# LUMINA_BOARD.net
KiCad netlist of a schematic drawn in EAGLE
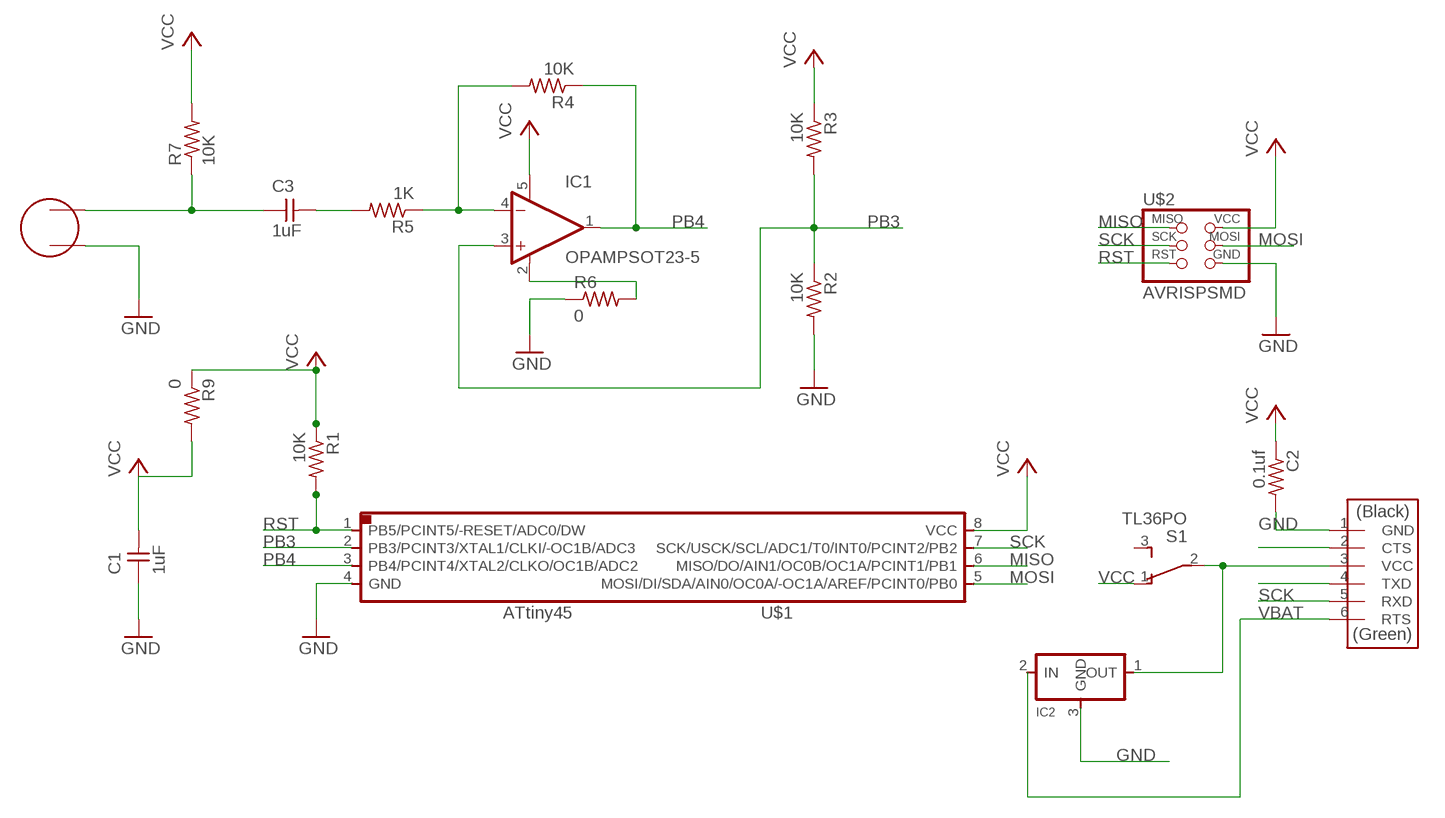
[diagram p0: schematic, sheet 1]

(export (version "E")
  (design (tool "Eeschema 10.0.6"))
  (components
    (comp (ref "C1")
      (value "1uF")
      (footprint "eagle-import:1206")
      (libsource (lib "eagle-import") (part "UNPOLARIZED_CAPACITOR1206"))
    )
    (comp (ref "C2")
      (value "0.1uf")
      (footprint "eagle-import:1206")
      (libsource (lib "eagle-import") (part "RESISTOR1206"))
    )
    (comp (ref "C3")
      (value "1uF")
      (footprint "eagle-import:1206")
      (libsource (lib "eagle-import") (part "UNPOLARIZED_CAPACITOR1206"))
    )
    (comp (ref "IC1")
      (value "OPAMPSOT23-5")
      (footprint "eagle-import:SOT23-5")
      (libsource (lib "eagle-import") (part "OPAMPSOT23-5"))
    )
    (comp (ref "IC2")
      (value "REGULATORSOT23")
      (footprint "eagle-import:SOT23")
      (libsource (lib "eagle-import") (part "REGULATORSOT23"))
    )
    (comp (ref "R1")
      (value "10K")
      (footprint "eagle-import:1206")
      (libsource (lib "eagle-import") (part "RESISTOR1206"))
    )
    (comp (ref "R2")
      (value "10K")
      (footprint "eagle-import:1206")
      (libsource (lib "eagle-import") (part "RESISTOR1206"))
    )
    (comp (ref "R3")
      (value "10K")
      (footprint "eagle-import:1206")
      (libsource (lib "eagle-import") (part "RESISTOR1206"))
    )
    (comp (ref "R4")
      (value "10K")
      (footprint "eagle-import:1206")
      (libsource (lib "eagle-import") (part "RESISTOR1206"))
    )
    (comp (ref "R5")
      (value "1K")
      (footprint "eagle-import:1206")
      (libsource (lib "eagle-import") (part "RESISTOR1206"))
    )
    (comp (ref "R6")
      (value "0")
      (footprint "eagle-import:1206")
      (libsource (lib "eagle-import") (part "RESISTOR1206"))
    )
    (comp (ref "R7")
      (value "10K")
      (footprint "eagle-import:1206")
      (libsource (lib "eagle-import") (part "RESISTOR1206"))
    )
    (comp (ref "R9")
      (value "0")
      (footprint "eagle-import:1206")
      (libsource (lib "eagle-import") (part "RESISTOR1206"))
    )
    (comp (ref "S1")
      (value "TL36PO")
      (footprint "eagle-import:TL3XPO")
      (libsource (lib "eagle-import") (part "TL36PO"))
    )
    (comp (ref "U$1")
      (value "ATTINY45SI")
      (footprint "eagle-import:SOIC8")
      (libsource (lib "eagle-import") (part "ATTINY45SI"))
    )
    (comp (ref "U$2")
      (value "AVRISPSMD")
      (footprint "eagle-import:2X03SMD")
      (libsource (lib "eagle-import") (part "AVRISPSMD"))
    )
    (comp (ref "U$3")
      (value "FTDI-SMD-HEADER")
      (footprint "eagle-import:1X06SMD")
      (libsource (lib "eagle-import") (part "FTDI-SMD-HEADER"))
    )
    (comp (ref "U$4")
      (value "ELECTRET")
      (footprint "eagle-import:ELECTRET_2742PBJ-A")
      (libsource (lib "eagle-import") (part "ELECTRET"))
    )
  )
  (nets
    (net (code "1") (name "/MISO") (class "Default")
      (node (ref "U$1") (pin "6") (pinfunction "MISO/DO/AIN1/OC0B/OC1A/PCINT1/PB1_6") (pintype "bidirectional"))
      (node (ref "U$2") (pin "1") (pinfunction "MISO_1") (pintype "passive"))
    )
    (net (code "2") (name "/MOSI") (class "Default")
      (node (ref "U$1") (pin "5") (pinfunction "MOSI/DI/SDA/AIN0/OC0A/-OC1A/AREF/PCINT0/PB0_5") (pintype "bidirectional"))
      (node (ref "U$2") (pin "4") (pinfunction "MOSI_4") (pintype "passive"))
    )
    (net (code "3") (name "/PB3") (class "Default")
      (node (ref "IC1") (pin "3") (pinfunction "+IN_3") (pintype "input"))
      (node (ref "R2") (pin "1") (pinfunction "1_1") (pintype "passive"))
      (node (ref "R3") (pin "2") (pinfunction "2_2") (pintype "passive"))
      (node (ref "U$1") (pin "2") (pinfunction "PB3/PCINT3/XTAL1/CLKI/-OC1B/ADC3_2") (pintype "bidirectional"))
    )
    (net (code "4") (name "/PB4") (class "Default")
      (node (ref "IC1") (pin "1") (pinfunction "OUT_1") (pintype "output"))
      (node (ref "R4") (pin "1") (pinfunction "1_1") (pintype "passive"))
      (node (ref "U$1") (pin "3") (pinfunction "PB4/PCINT4/XTAL2/CLKO/OC1B/ADC2_3") (pintype "bidirectional"))
    )
    (net (code "5") (name "/RST") (class "Default")
      (node (ref "R1") (pin "2") (pinfunction "2_2") (pintype "passive"))
      (node (ref "U$1") (pin "1") (pinfunction "PB5/PCINT5/-RESET/ADC0/DW_1") (pintype "bidirectional"))
      (node (ref "U$2") (pin "5") (pinfunction "RST_5") (pintype "passive"))
    )
    (net (code "6") (name "/SCK") (class "Default")
      (node (ref "U$1") (pin "7") (pinfunction "SCK/USCK/SCL/ADC1/T0/INT0/PCINT2/PB2_7") (pintype "bidirectional"))
      (node (ref "U$2") (pin "3") (pinfunction "SCK_3") (pintype "passive"))
      (node (ref "U$3") (pin "5") (pinfunction "RXD_5") (pintype "bidirectional"))
    )
    (net (code "7") (name "/VBAT") (class "Default")
      (node (ref "IC2") (pin "2") (pinfunction "IN_2") (pintype "bidirectional"))
      (node (ref "U$3") (pin "6") (pinfunction "RTS_6") (pintype "bidirectional"))
    )
    (net (code "8") (name "GND") (class "Default")
      (node (ref "C1") (pin "1") (pinfunction "1_1") (pintype "passive"))
      (node (ref "C2") (pin "2") (pinfunction "2_2") (pintype "passive"))
      (node (ref "IC2") (pin "3") (pinfunction "GND_3") (pintype "bidirectional"))
      (node (ref "R2") (pin "2") (pinfunction "2_2") (pintype "passive"))
      (node (ref "R6") (pin "1") (pinfunction "1_1") (pintype "passive"))
      (node (ref "U$1") (pin "4") (pinfunction "GND_4") (pintype "bidirectional"))
      (node (ref "U$2") (pin "6") (pinfunction "GND_6") (pintype "passive"))
      (node (ref "U$3") (pin "1") (pinfunction "GND_1") (pintype "bidirectional"))
      (node (ref "U$4") (pin "P$1") (pinfunction "P$1_P$1") (pintype "bidirectional"))
    )
    (net (code "9") (name "Net-(C3-Pad1)") (class "Default")
      (node (ref "C3") (pin "1") (pinfunction "1_1") (pintype "passive"))
      (node (ref "R7") (pin "1") (pinfunction "1_1") (pintype "passive"))
      (node (ref "U$4") (pin "P$2") (pinfunction "P$2_P$2") (pintype "bidirectional"))
    )
    (net (code "10") (name "Net-(C3-Pad2)") (class "Default")
      (node (ref "C3") (pin "2") (pinfunction "2_2") (pintype "passive"))
      (node (ref "R5") (pin "2") (pinfunction "2_2") (pintype "passive"))
    )
    (net (code "11") (name "Net-(IC1--IN)") (class "Default")
      (node (ref "IC1") (pin "4") (pinfunction "-IN_4") (pintype "input"))
      (node (ref "R4") (pin "2") (pinfunction "2_2") (pintype "passive"))
      (node (ref "R5") (pin "1") (pinfunction "1_1") (pintype "passive"))
    )
    (net (code "12") (name "Net-(IC1-V-)") (class "Default")
      (node (ref "IC1") (pin "2") (pinfunction "V-_2") (pintype "power_in"))
      (node (ref "R6") (pin "2") (pinfunction "2_2") (pintype "passive"))
    )
    (net (code "13") (name "Net-(IC2-OUT)") (class "Default")
      (node (ref "IC2") (pin "1") (pinfunction "OUT_1") (pintype "bidirectional"))
      (node (ref "S1") (pin "2") (pinfunction "P_2") (pintype "passive"))
      (node (ref "U$3") (pin "3") (pinfunction "VCC_3") (pintype "bidirectional"))
    )
    (net (code "14") (name "VCC") (class "Default")
      (node (ref "C1") (pin "2") (pinfunction "2_2") (pintype "passive"))
      (node (ref "C2") (pin "1") (pinfunction "1_1") (pintype "passive"))
      (node (ref "IC1") (pin "5") (pinfunction "V+_5") (pintype "power_in"))
      (node (ref "R1") (pin "1") (pinfunction "1_1") (pintype "passive"))
      (node (ref "R3") (pin "1") (pinfunction "1_1") (pintype "passive"))
      (node (ref "R7") (pin "2") (pinfunction "2_2") (pintype "passive"))
      (node (ref "R9") (pin "1") (pinfunction "1_1") (pintype "passive"))
      (node (ref "R9") (pin "2") (pinfunction "2_2") (pintype "passive"))
      (node (ref "S1") (pin "1") (pinfunction "O_1") (pintype "passive"))
      (node (ref "U$1") (pin "8") (pinfunction "VCC_8") (pintype "bidirectional"))
      (node (ref "U$2") (pin "2") (pinfunction "VCC_2") (pintype "passive"))
    )
    (net (code "15") (name "unconnected-(S1-S-Pad3)") (class "Default")
      (node (ref "S1") (pin "3") (pinfunction "S_3") (pintype "passive"))
    )
    (net (code "16") (name "unconnected-(U$3-CTS-Pad2)") (class "Default")
      (node (ref "U$3") (pin "2") (pinfunction "CTS_2") (pintype "bidirectional"))
    )
    (net (code "17") (name "unconnected-(U$3-TXD-Pad4)") (class "Default")
      (node (ref "U$3") (pin "4") (pinfunction "TXD_4") (pintype "bidirectional"))
    )
  )
)
